# Lumiboard_-_sensor_module_rev_C.net
KiCad netlist of a schematic drawn in EAGLE
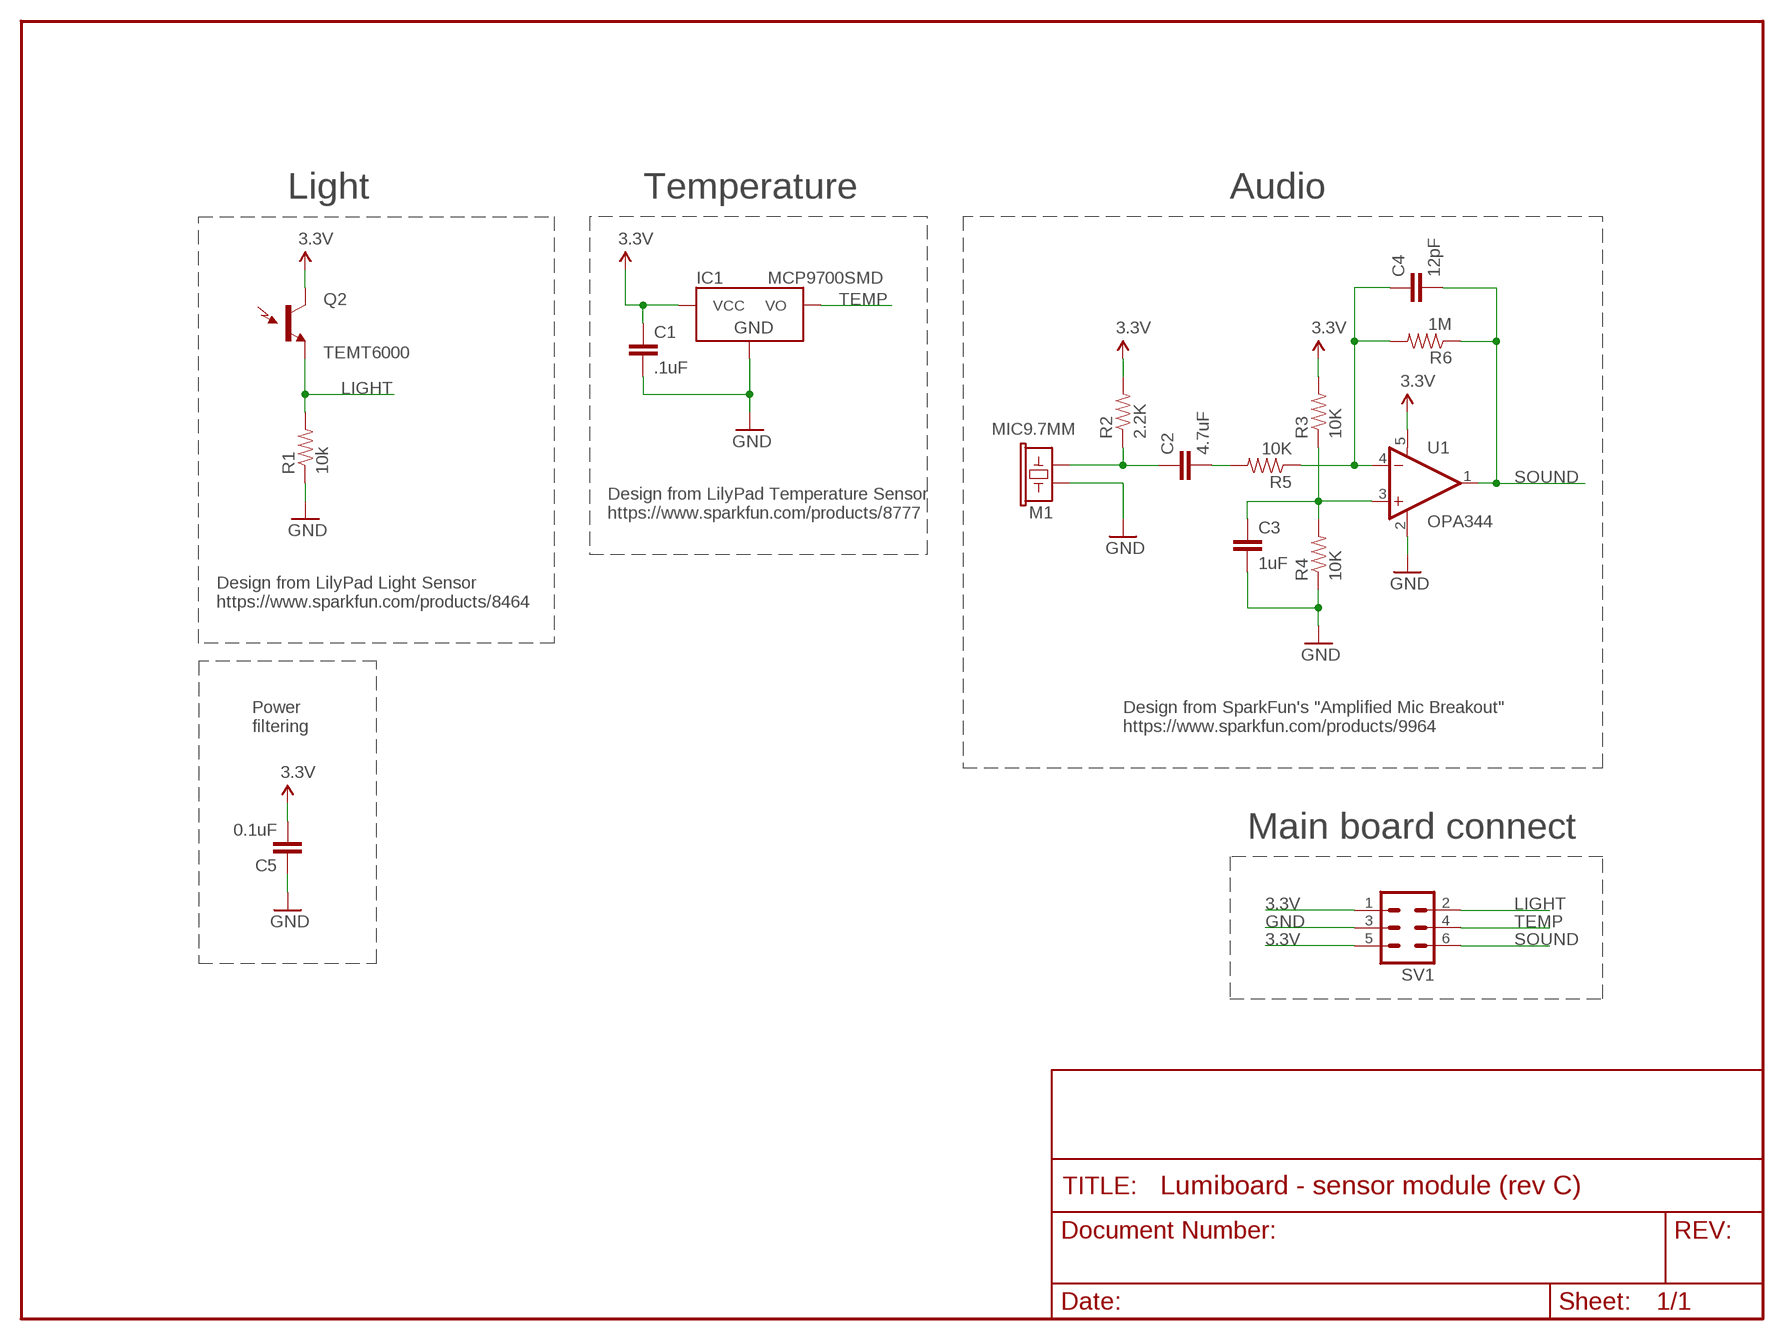
[diagram p0: schematic, sheet 1]

(export (version "E")
  (design (tool "Eeschema 10.0.6"))
  (components
    (comp (ref "C1")
      (value ".1uF")
      (footprint "eagle-import:0805")
      (libsource (lib "eagle-import") (part "CAP0805"))
    )
    (comp (ref "C2")
      (value "4.7uF")
      (footprint "eagle-import:0805")
      (libsource (lib "eagle-import") (part "SparkFun-Capacitors_CAP0805"))
    )
    (comp (ref "C3")
      (value "1uF")
      (footprint "eagle-import:0805")
      (libsource (lib "eagle-import") (part "SparkFun-Capacitors_CAP0805"))
    )
    (comp (ref "C4")
      (value "12pF")
      (footprint "eagle-import:0805")
      (libsource (lib "eagle-import") (part "SparkFun-Capacitors_CAP0805"))
    )
    (comp (ref "C5")
      (value "0.1uF")
      (footprint "eagle-import:0805")
      (libsource (lib "eagle-import") (part "SparkFun-Capacitors_CAP0805"))
    )
    (comp (ref "IC1")
      (value "MCP9700SMD")
      (footprint "eagle-import:SOT23-3")
      (libsource (lib "eagle-import") (part "MCP9700SMD"))
    )
    (comp (ref "M1")
      (value "MIC9.7MM")
      (footprint "eagle-import:MIC-9.7MM")
      (libsource (lib "eagle-import") (part "MIC9.7MM"))
    )
    (comp (ref "Q2")
      (value "TEMT6000")
      (footprint "eagle-import:TEMT6000-SEN")
      (libsource (lib "eagle-import") (part "TEMT6000"))
    )
    (comp (ref "R1")
      (value "10k")
      (footprint "eagle-import:0805")
      (libsource (lib "eagle-import") (part "RESISTOR0805-RES"))
    )
    (comp (ref "R2")
      (value "2.2K")
      (footprint "eagle-import:0805")
      (libsource (lib "eagle-import") (part "RESISTOR0805-RES"))
    )
    (comp (ref "R3")
      (value "10K")
      (footprint "eagle-import:0805")
      (libsource (lib "eagle-import") (part "RESISTOR0805-RES"))
    )
    (comp (ref "R4")
      (value "10K")
      (footprint "eagle-import:0805")
      (libsource (lib "eagle-import") (part "RESISTOR0805-RES"))
    )
    (comp (ref "R5")
      (value "10K")
      (footprint "eagle-import:0805")
      (libsource (lib "eagle-import") (part "RESISTOR0805-RES"))
    )
    (comp (ref "R6")
      (value "1M")
      (footprint "eagle-import:0805")
      (libsource (lib "eagle-import") (part "RESISTOR0805-RES"))
    )
    (comp (ref "SV1")
      (value "ML6")
      (footprint "eagle-import:ML6")
      (libsource (lib "eagle-import") (part "ML6"))
    )
    (comp (ref "U1")
      (value "OPA344")
      (footprint "eagle-import:SOT23-5")
      (libsource (lib "eagle-import") (part "OPA344"))
    )
  )
  (nets
    (net (code "1") (name "/LIGHT") (class "Default")
      (node (ref "Q2") (pin "EMITTER") (pinfunction "E1_EMITTER") (pintype "passive"))
      (node (ref "R1") (pin "2") (pinfunction "2_2") (pintype "passive"))
      (node (ref "SV1") (pin "2") (pinfunction "2_2") (pintype "passive"))
    )
    (net (code "2") (name "/SOUND") (class "Default")
      (node (ref "C4") (pin "2") (pinfunction "2_2") (pintype "passive"))
      (node (ref "R6") (pin "1") (pinfunction "1_1") (pintype "passive"))
      (node (ref "SV1") (pin "6") (pinfunction "6_6") (pintype "passive"))
      (node (ref "U1") (pin "1") (pinfunction "OUT_1") (pintype "output"))
    )
    (net (code "3") (name "/TEMP") (class "Default")
      (node (ref "IC1") (pin "2") (pinfunction "VO_2") (pintype "bidirectional"))
      (node (ref "SV1") (pin "4") (pinfunction "4_4") (pintype "passive"))
    )
    (net (code "4") (name "3.3V") (class "Default")
      (node (ref "C1") (pin "1") (pinfunction "1_1") (pintype "passive"))
      (node (ref "C5") (pin "2") (pinfunction "2_2") (pintype "passive"))
      (node (ref "IC1") (pin "1") (pinfunction "VCC_1") (pintype "bidirectional"))
      (node (ref "Q2") (pin "COLLECTOR") (pinfunction "C1_COLLECTOR") (pintype "passive"))
      (node (ref "R2") (pin "2") (pinfunction "2_2") (pintype "passive"))
      (node (ref "R3") (pin "2") (pinfunction "2_2") (pintype "passive"))
      (node (ref "SV1") (pin "1") (pinfunction "1_1") (pintype "passive"))
      (node (ref "SV1") (pin "5") (pinfunction "5_5") (pintype "passive"))
      (node (ref "U1") (pin "5") (pinfunction "V+_5") (pintype "power_in"))
    )
    (net (code "5") (name "GND") (class "Default")
      (node (ref "C1") (pin "2") (pinfunction "2_2") (pintype "passive"))
      (node (ref "C3") (pin "2") (pinfunction "2_2") (pintype "passive"))
      (node (ref "C5") (pin "1") (pinfunction "1_1") (pintype "passive"))
      (node (ref "IC1") (pin "3") (pinfunction "GND_3") (pintype "bidirectional"))
      (node (ref "M1") (pin "2") (pinfunction "2_2") (pintype "passive"))
      (node (ref "R1") (pin "1") (pinfunction "1_1") (pintype "passive"))
      (node (ref "R4") (pin "1") (pinfunction "1_1") (pintype "passive"))
      (node (ref "SV1") (pin "3") (pinfunction "3_3") (pintype "passive"))
      (node (ref "U1") (pin "2") (pinfunction "V-_2") (pintype "power_in"))
    )
    (net (code "6") (name "Net-(C2-Pad1)") (class "Default")
      (node (ref "C2") (pin "1") (pinfunction "1_1") (pintype "passive"))
      (node (ref "M1") (pin "1") (pinfunction "1_1") (pintype "passive"))
      (node (ref "R2") (pin "1") (pinfunction "1_1") (pintype "passive"))
    )
    (net (code "7") (name "Net-(C2-Pad2)") (class "Default")
      (node (ref "C2") (pin "2") (pinfunction "2_2") (pintype "passive"))
      (node (ref "R5") (pin "2") (pinfunction "2_2") (pintype "passive"))
    )
    (net (code "8") (name "Net-(U1-+IN)") (class "Default")
      (node (ref "C3") (pin "1") (pinfunction "1_1") (pintype "passive"))
      (node (ref "R3") (pin "1") (pinfunction "1_1") (pintype "passive"))
      (node (ref "R4") (pin "2") (pinfunction "2_2") (pintype "passive"))
      (node (ref "U1") (pin "3") (pinfunction "+IN_3") (pintype "input"))
    )
    (net (code "9") (name "Net-(U1--IN)") (class "Default")
      (node (ref "C4") (pin "1") (pinfunction "1_1") (pintype "passive"))
      (node (ref "R5") (pin "1") (pinfunction "1_1") (pintype "passive"))
      (node (ref "R6") (pin "2") (pinfunction "2_2") (pintype "passive"))
      (node (ref "U1") (pin "4") (pinfunction "-IN_4") (pintype "input"))
    )
  )
)
